# 04_MAIN_POWER.net
KiCad netlist of a schematic drawn in Altium Designer
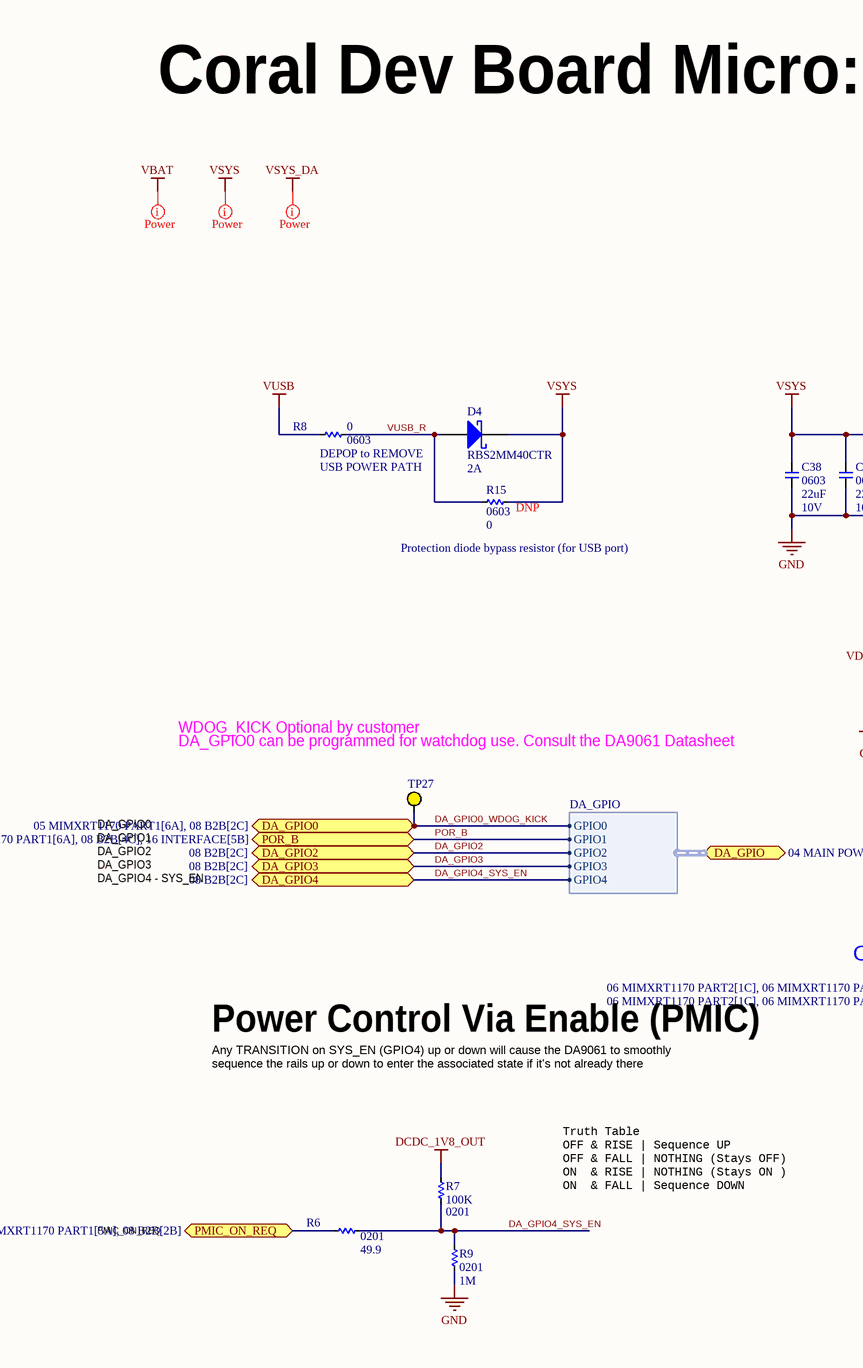
[diagram p0: 04 MAIN POWER.SchDoc, left]
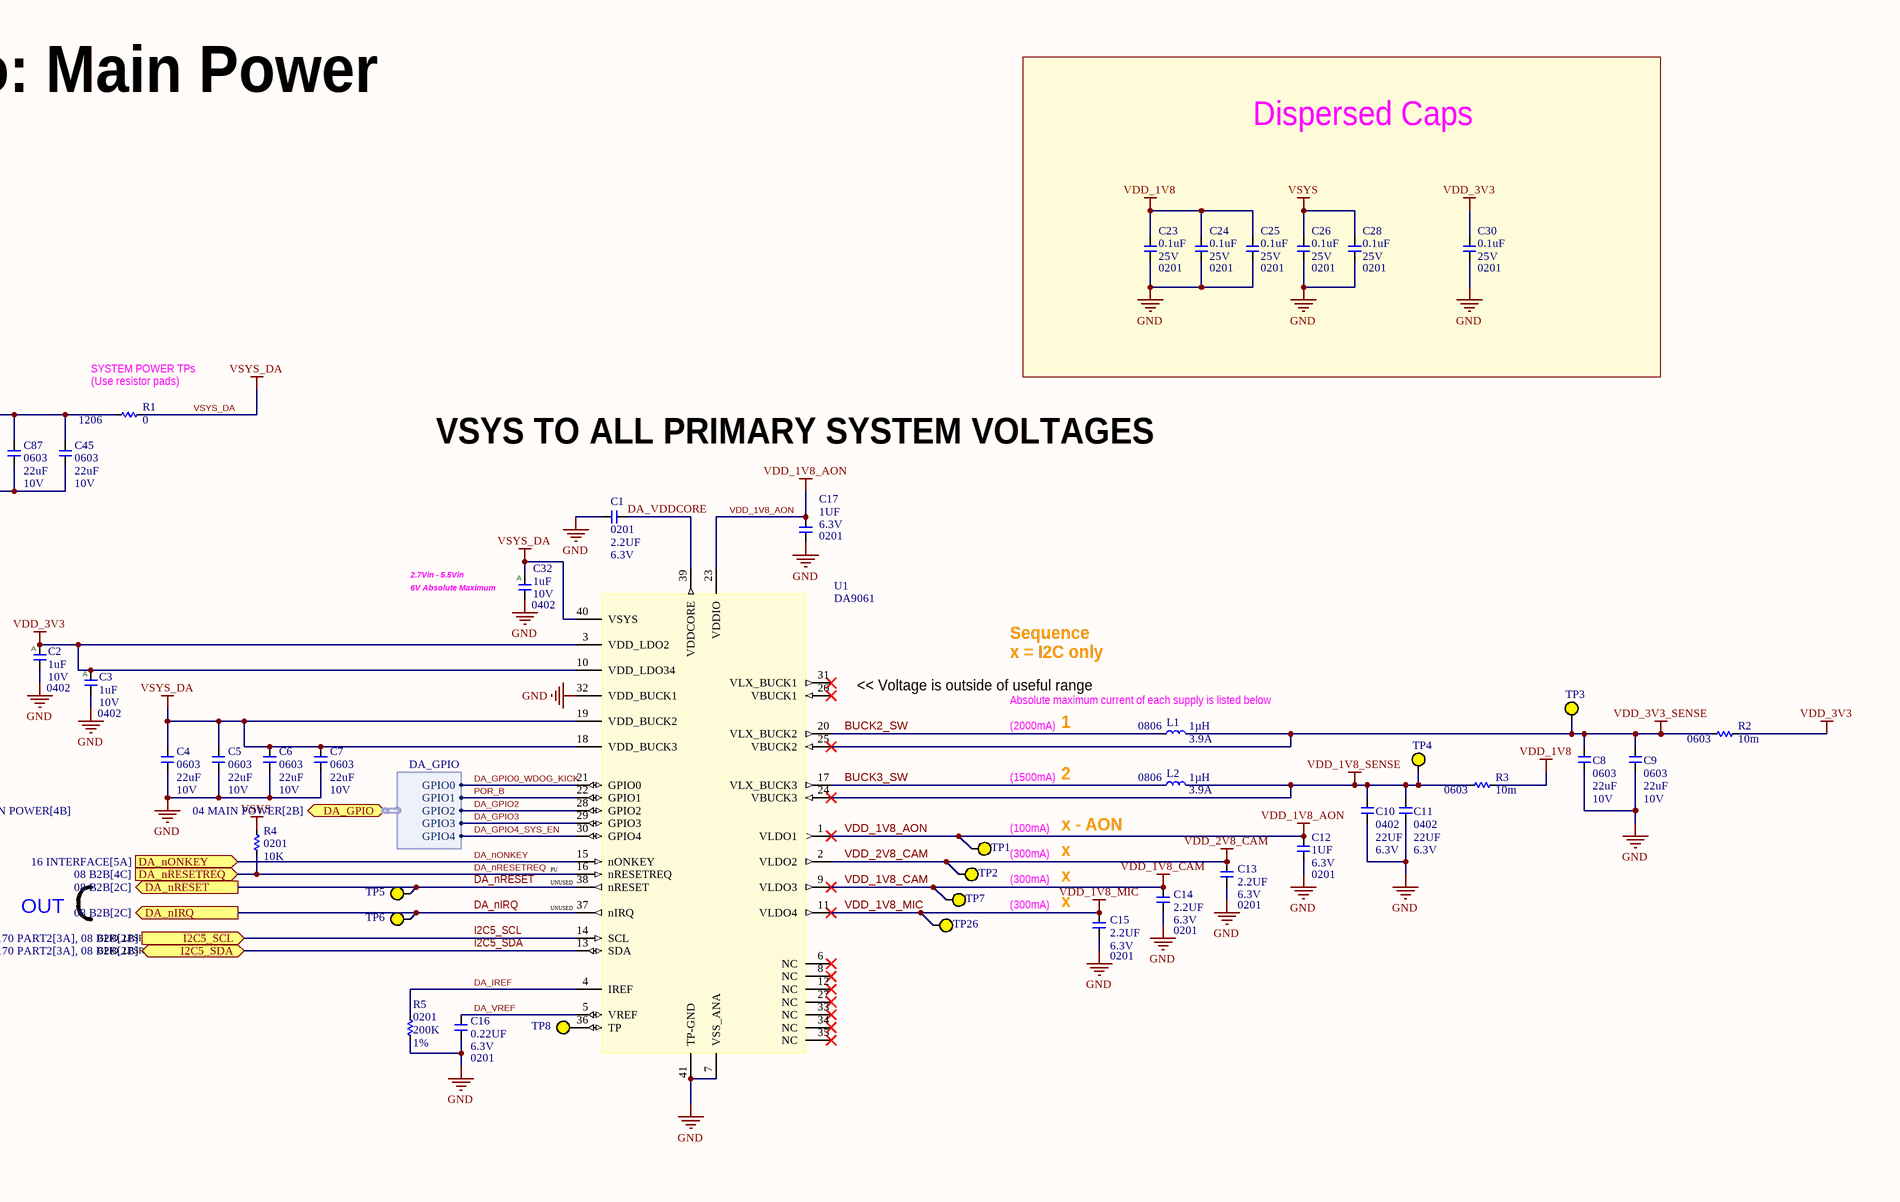
[diagram p1: 04 MAIN POWER.SchDoc, right]

(export (version "E")
  (design (tool "Eeschema 10.0.6"))
  (components
    (comp (ref "C1")
      (value "2.2UF")
      (footprint "C0201_H0.39MM")
      (description "CAP, CER, X5R, 2.2uF, 20%, 6.3V, 0201, 0.39mm")
      (fields
        (field (name "MFG") "YAGEO")
        (field (name "PACKAGE") "0201")
        (field (name "VOLTAGE") "6.3V")
        (field (name "TOLERANCE") "20%")
      )
      (libsource (lib "AltiumReleaseLibDB") (part "__Template_Cap"))
    )
    (comp (ref "C2")
      (value "1uF")
      (footprint "C0402")
      (description "CAP, CER, X5R, 1uF, 10V, 10%, 0402, AUTOGRADE")
      (fields
        (field (name "MFG") "Taiyo Yuden")
        (field (name "PACKAGE") "0402")
        (field (name "VOLTAGE") "10V")
        (field (name "TOLERANCE") "10%")
      )
      (libsource (lib "AltiumReleaseLibDB") (part "__Template_Cap_Auto"))
    )
    (comp (ref "C3")
      (value "1uF")
      (footprint "C0402")
      (description "CAP, CER, X5R, 1uF, 10V, 10%, 0402, AUTOGRADE")
      (fields
        (field (name "MFG") "Taiyo Yuden")
        (field (name "PACKAGE") "0402")
        (field (name "VOLTAGE") "10V")
        (field (name "TOLERANCE") "10%")
      )
      (libsource (lib "AltiumReleaseLibDB") (part "__Template_Cap_Auto"))
    )
    (comp (ref "C4")
      (value "22uF")
      (footprint "C0603")
      (description "CAP, CER, X5R, 22uF, 20%, 10V, 0603")
      (fields
        (field (name "MFG") "TDK")
        (field (name "PACKAGE") "0603")
        (field (name "VOLTAGE") "10V")
        (field (name "TOLERANCE") "20%")
      )
      (libsource (lib "AltiumReleaseLibDB") (part "__Template_Cap"))
    )
    (comp (ref "C5")
      (value "22uF")
      (footprint "C0603")
      (description "CAP, CER, X5R, 22uF, 20%, 10V, 0603")
      (fields
        (field (name "MFG") "TDK")
        (field (name "PACKAGE") "0603")
        (field (name "VOLTAGE") "10V")
        (field (name "TOLERANCE") "20%")
      )
      (libsource (lib "AltiumReleaseLibDB") (part "__Template_Cap"))
    )
    (comp (ref "C6")
      (value "22uF")
      (footprint "C0603")
      (description "CAP, CER, X5R, 22uF, 20%, 10V, 0603")
      (fields
        (field (name "MFG") "TDK")
        (field (name "PACKAGE") "0603")
        (field (name "VOLTAGE") "10V")
        (field (name "TOLERANCE") "20%")
      )
      (libsource (lib "AltiumReleaseLibDB") (part "__Template_Cap"))
    )
    (comp (ref "C7")
      (value "22uF")
      (footprint "C0603")
      (description "CAP, CER, X5R, 22uF, 20%, 10V, 0603")
      (fields
        (field (name "MFG") "TDK")
        (field (name "PACKAGE") "0603")
        (field (name "VOLTAGE") "10V")
        (field (name "TOLERANCE") "20%")
      )
      (libsource (lib "AltiumReleaseLibDB") (part "__Template_Cap"))
    )
    (comp (ref "C8")
      (value "22uF")
      (footprint "C0603")
      (description "CAP, CER, X5R, 22uF, 20%, 10V, 0603")
      (fields
        (field (name "MFG") "TDK")
        (field (name "PACKAGE") "0603")
        (field (name "VOLTAGE") "10V")
        (field (name "TOLERANCE") "20%")
      )
      (libsource (lib "AltiumReleaseLibDB") (part "__Template_Cap"))
    )
    (comp (ref "C9")
      (value "22uF")
      (footprint "C0603")
      (description "CAP, CER, X5R, 22uF, 20%, 10V, 0603")
      (fields
        (field (name "MFG") "TDK")
        (field (name "PACKAGE") "0603")
        (field (name "VOLTAGE") "10V")
        (field (name "TOLERANCE") "20%")
      )
      (libsource (lib "AltiumReleaseLibDB") (part "__Template_Cap"))
    )
    (comp (ref "C10")
      (value "22UF")
      (footprint "C0402")
      (description "CAP, CER, X5R, 22uF, 20%, 6.3V, 0402")
      (fields
        (field (name "MFG") "AVX")
        (field (name "PACKAGE") "0402")
        (field (name "VOLTAGE") "6.3V")
        (field (name "TOLERANCE") "20%")
      )
      (libsource (lib "AltiumReleaseLibDB") (part "__Template_Cap"))
    )
    (comp (ref "C11")
      (value "22UF")
      (footprint "C0402")
      (description "CAP, CER, X5R, 22uF, 20%, 6.3V, 0402")
      (fields
        (field (name "MFG") "AVX")
        (field (name "PACKAGE") "0402")
        (field (name "VOLTAGE") "6.3V")
        (field (name "TOLERANCE") "20%")
      )
      (libsource (lib "AltiumReleaseLibDB") (part "__Template_Cap"))
    )
    (comp (ref "C12")
      (value "1UF")
      (footprint "C0201_H0.39MM")
      (description "CAP, CER, X6S, 1uF, 20%, 6.3V, 0201, 0.39mm")
      (fields
        (field (name "MFG") "MURATA")
        (field (name "PACKAGE") "0201")
        (field (name "VOLTAGE") "6.3V")
        (field (name "TOLERANCE") "20%")
      )
      (libsource (lib "AltiumReleaseLibDB") (part "__Template_Cap"))
    )
    (comp (ref "C13")
      (value "2.2UF")
      (footprint "C0201_H0.39MM")
      (description "CAP, CER, X5R, 2.2uF, 20%, 6.3V, 0201, 0.39mm")
      (fields
        (field (name "MFG") "YAGEO")
        (field (name "PACKAGE") "0201")
        (field (name "VOLTAGE") "6.3V")
        (field (name "TOLERANCE") "20%")
      )
      (libsource (lib "AltiumReleaseLibDB") (part "__Template_Cap"))
    )
    (comp (ref "C14")
      (value "2.2UF")
      (footprint "C0201_H0.39MM")
      (description "CAP, CER, X5R, 2.2uF, 20%, 6.3V, 0201, 0.39mm")
      (fields
        (field (name "MFG") "YAGEO")
        (field (name "PACKAGE") "0201")
        (field (name "VOLTAGE") "6.3V")
        (field (name "TOLERANCE") "20%")
      )
      (libsource (lib "AltiumReleaseLibDB") (part "__Template_Cap"))
    )
    (comp (ref "C15")
      (value "2.2UF")
      (footprint "C0201_H0.39MM")
      (description "CAP, CER, X5R, 2.2uF, 20%, 6.3V, 0201, 0.39mm")
      (fields
        (field (name "MFG") "YAGEO")
        (field (name "PACKAGE") "0201")
        (field (name "VOLTAGE") "6.3V")
        (field (name "TOLERANCE") "20%")
      )
      (libsource (lib "AltiumReleaseLibDB") (part "__Template_Cap"))
    )
    (comp (ref "C16")
      (value "0.22UF")
      (footprint "C0201")
      (description "CAP, CER, X5R, 0.22uF, 6.3V, 10%, 0201, 0.33mm T")
      (fields
        (field (name "MFG") "TDK")
        (field (name "PACKAGE") "0201")
        (field (name "VOLTAGE") "6.3V")
        (field (name "TOLERANCE") "10%")
      )
      (libsource (lib "AltiumReleaseLibDB") (part "__Template_Cap"))
    )
    (comp (ref "C17")
      (value "1UF")
      (footprint "C0201_H0.39MM")
      (description "CAP, CER, X6S, 1uF, 20%, 6.3V, 0201, 0.39mm")
      (fields
        (field (name "MFG") "MURATA")
        (field (name "PACKAGE") "0201")
        (field (name "VOLTAGE") "6.3V")
        (field (name "TOLERANCE") "20%")
      )
      (libsource (lib "AltiumReleaseLibDB") (part "__Template_Cap"))
    )
    (comp (ref "C23")
      (value "0.1uF")
      (footprint "C0201Y")
      (description "CAP, CER, X5R, 0.1uF, 25V, 20%, 0201, 0.33mm T")
      (fields
        (field (name "MFG") "MURATA")
        (field (name "PACKAGE") "0201")
        (field (name "VOLTAGE") "25V")
        (field (name "TOLERANCE") "20%")
      )
      (libsource (lib "AltiumReleaseLibDB") (part "__Template_Cap"))
    )
    (comp (ref "C24")
      (value "0.1uF")
      (footprint "C0201Y")
      (description "CAP, CER, X5R, 0.1uF, 25V, 20%, 0201, 0.33mm T")
      (fields
        (field (name "MFG") "MURATA")
        (field (name "PACKAGE") "0201")
        (field (name "VOLTAGE") "25V")
        (field (name "TOLERANCE") "20%")
      )
      (libsource (lib "AltiumReleaseLibDB") (part "__Template_Cap"))
    )
    (comp (ref "C25")
      (value "0.1uF")
      (footprint "C0201Y")
      (description "CAP, CER, X5R, 0.1uF, 25V, 20%, 0201, 0.33mm T")
      (fields
        (field (name "MFG") "MURATA")
        (field (name "PACKAGE") "0201")
        (field (name "VOLTAGE") "25V")
        (field (name "TOLERANCE") "20%")
      )
      (libsource (lib "AltiumReleaseLibDB") (part "__Template_Cap"))
    )
    (comp (ref "C26")
      (value "0.1uF")
      (footprint "C0201Y")
      (description "CAP, CER, X5R, 0.1uF, 25V, 20%, 0201, 0.33mm T")
      (fields
        (field (name "MFG") "MURATA")
        (field (name "PACKAGE") "0201")
        (field (name "VOLTAGE") "25V")
        (field (name "TOLERANCE") "20%")
      )
      (libsource (lib "AltiumReleaseLibDB") (part "__Template_Cap"))
    )
    (comp (ref "C28")
      (value "0.1uF")
      (footprint "C0201Y")
      (description "CAP, CER, X5R, 0.1uF, 25V, 20%, 0201, 0.33mm T")
      (fields
        (field (name "MFG") "MURATA")
        (field (name "PACKAGE") "0201")
        (field (name "VOLTAGE") "25V")
        (field (name "TOLERANCE") "20%")
      )
      (libsource (lib "AltiumReleaseLibDB") (part "__Template_Cap"))
    )
    (comp (ref "C30")
      (value "0.1uF")
      (footprint "C0201Y")
      (description "CAP, CER, X5R, 0.1uF, 25V, 20%, 0201, 0.33mm T")
      (fields
        (field (name "MFG") "MURATA")
        (field (name "PACKAGE") "0201")
        (field (name "VOLTAGE") "25V")
        (field (name "TOLERANCE") "20%")
      )
      (libsource (lib "AltiumReleaseLibDB") (part "__Template_Cap"))
    )
    (comp (ref "C32")
      (value "1uF")
      (footprint "C0402")
      (description "CAP, CER, X5R, 1uF, 10V, 10%, 0402, AUTOGRADE")
      (fields
        (field (name "MFG") "Taiyo Yuden")
        (field (name "PACKAGE") "0402")
        (field (name "VOLTAGE") "10V")
        (field (name "TOLERANCE") "10%")
      )
      (libsource (lib "AltiumReleaseLibDB") (part "__Template_Cap_Auto"))
    )
    (comp (ref "C38")
      (value "22uF")
      (footprint "C0603")
      (description "CAP, CER, X5R, 22uF, 20%, 10V, 0603")
      (fields
        (field (name "MFG") "TDK")
        (field (name "PACKAGE") "0603")
        (field (name "VOLTAGE") "10V")
        (field (name "TOLERANCE") "20%")
      )
      (libsource (lib "AltiumReleaseLibDB") (part "__Template_Cap"))
    )
    (comp (ref "C45")
      (value "22uF")
      (footprint "C0603")
      (description "CAP, CER, X5R, 22uF, 20%, 10V, 0603")
      (fields
        (field (name "MFG") "TDK")
        (field (name "PACKAGE") "0603")
        (field (name "VOLTAGE") "10V")
        (field (name "TOLERANCE") "20%")
      )
      (libsource (lib "AltiumReleaseLibDB") (part "__Template_Cap"))
    )
    (comp (ref "C87")
      (value "22uF")
      (footprint "C0603")
      (description "CAP, CER, X5R, 22uF, 20%, 10V, 0603")
      (fields
        (field (name "MFG") "TDK")
        (field (name "PACKAGE") "0603")
        (field (name "VOLTAGE") "10V")
        (field (name "TOLERANCE") "20%")
      )
      (libsource (lib "AltiumReleaseLibDB") (part "__Template_Cap"))
    )
    (comp (ref "D4")
      (value "RBS2MM40CTR")
      (footprint "SOD123_AK")
      (description "DIODE, SCHOTTKY, 20V VRRM, 2A IO, 45A SURGE, SOD-123F")
      (fields
        (field (name "MFG") "Rohm Semiconductor")
        (field (name "CURRENT - AVERAGE RECTIFIED (IO)") "2A")
        (field (name "Comment") "__Template_DIODE_SCHOTTKY")
      )
      (libsource (lib "AltiumReleaseLibDB") (part "__Template_DIODE_SCHOTTKY"))
    )
    (comp (ref "L1")
      (value "1µH")
      (footprint "L2016_H1.0MM")
      (description "IND, PWR, FILM, 1uH, 20%, 3.9A Isat, 3.1A Idc, 0.056 DCR, 2016m, 1.00mm")
      (fields
        (field (name "MFG") "TDK")
        (field (name "PACKAGE") "0806")
        (field (name "TOLERANCE") "20")
        (field (name "ISAT") "3.9A")
      )
      (libsource (lib "AltiumReleaseLibDB") (part "__Template_Inductor"))
    )
    (comp (ref "L2")
      (value "1µH")
      (footprint "L2016_H1.0MM")
      (description "IND, PWR, FILM, 1uH, 20%, 3.9A Isat, 3.1A Idc, 0.056 DCR, 2016m, 1.00mm")
      (fields
        (field (name "MFG") "TDK")
        (field (name "PACKAGE") "0806")
        (field (name "TOLERANCE") "20")
        (field (name "ISAT") "3.9A")
      )
      (libsource (lib "AltiumReleaseLibDB") (part "__Template_Inductor"))
    )
    (comp (ref "R1")
      (value "0")
      (footprint "R1206")
      (description "RES, 0, 5%, 1/4W, 1206")
      (fields (field (name "MFG") "ROHM") (field (name "PACKAGE") "1206") (field (name "POWER") "1/4W"))
      (libsource (lib "AltiumReleaseLibDB") (part "__Template_Resistor"))
    )
    (comp (ref "R2")
      (value "10m")
      (footprint "R0603")
      (description "Resistor, 10.0m Ohms, 0603, 0.1W, ±1%")
      (fields (field (name "MFG") "VISHAY") (field (name "PACKAGE") "0603") (field (name "POWER") "1/10W"))
      (libsource (lib "AltiumReleaseLibDB") (part "__Template_Resistor"))
    )
    (comp (ref "R3")
      (value "10m")
      (footprint "R0603")
      (description "Resistor, 10.0m Ohms, 0603, 0.1W, ±1%")
      (fields (field (name "MFG") "VISHAY") (field (name "PACKAGE") "0603") (field (name "POWER") "1/10W"))
      (libsource (lib "AltiumReleaseLibDB") (part "__Template_Resistor"))
    )
    (comp (ref "R4")
      (value "10K")
      (footprint "R0201")
      (description "RES, 10K, 1%, 1/20W, 0201")
      (fields (field (name "MFG") "YAGEO") (field (name "PACKAGE") "0201") (field (name "POWER") "1/20W"))
      (libsource (lib "AltiumReleaseLibDB") (part "__Template_Resistor"))
    )
    (comp (ref "R5")
      (value "200K")
      (footprint "R0201")
      (description "Resistor, 200K Ohms, 0201, 0.05W, ±1%")
      (fields
        (field (name "MFG") "VISHAY")
        (field (name "PACKAGE") "0201")
        (field (name "POWER") "1/20W")
        (field (name "TOLERANCE") "1%")
      )
      (libsource (lib "AltiumReleaseLibDB") (part "__Template_Resistor"))
    )
    (comp (ref "R6")
      (value "49.9")
      (footprint "R0201")
      (description "RES, 49.9, 1%, 1/20W, 0201")
      (fields (field (name "MFG") "PANASONIC") (field (name "PACKAGE") "0201") (field (name "POWER") "1/20W"))
      (libsource (lib "AltiumReleaseLibDB") (part "__Template_Resistor"))
    )
    (comp (ref "R7")
      (value "100K")
      (footprint "R0201")
      (description "RES, 100K, 1%, 1/20W, 0201")
      (fields (field (name "MFG") "PANASONIC") (field (name "PACKAGE") "0201") (field (name "POWER") "1/20W"))
      (libsource (lib "AltiumReleaseLibDB") (part "__Template_Resistor"))
    )
    (comp (ref "R8")
      (value "0")
      (footprint "R0603")
      (description "RES, 0, JUMPER, 1/8W, 0603")
      (fields (field (name "MFG") "VISHAY") (field (name "PACKAGE") "0603") (field (name "POWER") "1/8W"))
      (libsource (lib "AltiumReleaseLibDB") (part "__Template_Resistor"))
    )
    (comp (ref "R9")
      (value "1M")
      (footprint "R0201")
      (description "RES, 1M, 1%, 1/20W, 0201")
      (fields (field (name "MFG") "PANASONIC") (field (name "PACKAGE") "0201") (field (name "POWER") "1/20W"))
      (libsource (lib "AltiumReleaseLibDB") (part "__Template_Resistor"))
    )
    (comp (ref "R15")
      (value "0")
      (footprint "R0603")
      (description "RES, 0, JUMPER, 1/8W, 0603")
      (fields
        (field (name "MFG") "VISHAY")
        (field (name "PACKAGE") "0603")
        (field (name "POWER") "1/8W")
        (field (name "DNP") "DNP")
      )
      (libsource (lib "AltiumReleaseLibDB") (part "__Template_Resistor"))
    )
    (comp (ref "TP1")
      (value "TESTPAD_30MIL")
      (footprint "TESTPAD_SMT_30MIL")
      (description "TESTPAD_SMT_30MIL")
      (fields (field (name "MFG") "_PCB Feature"))
      (libsource (lib "AltiumReleaseLibDB") (part "TESTPAD_30MIL"))
    )
    (comp (ref "TP2")
      (value "TESTPAD_30MIL")
      (footprint "TESTPAD_SMT_30MIL")
      (description "TESTPAD_SMT_30MIL")
      (fields (field (name "MFG") "_PCB Feature"))
      (libsource (lib "AltiumReleaseLibDB") (part "TESTPAD_30MIL"))
    )
    (comp (ref "TP3")
      (value "TESTPAD_30MIL")
      (footprint "TESTPAD_SMT_30MIL")
      (description "TESTPAD_SMT_30MIL")
      (fields (field (name "MFG") "_PCB Feature"))
      (libsource (lib "AltiumReleaseLibDB") (part "TESTPAD_30MIL"))
    )
    (comp (ref "TP4")
      (value "TESTPAD_30MIL")
      (footprint "TESTPAD_SMT_30MIL")
      (description "TESTPAD_SMT_30MIL")
      (fields (field (name "MFG") "_PCB Feature"))
      (libsource (lib "AltiumReleaseLibDB") (part "TESTPAD_30MIL"))
    )
    (comp (ref "TP5")
      (value "TESTPAD_30MIL")
      (footprint "TESTPAD_SMT_30MIL")
      (description "TESTPAD_SMT_30MIL")
      (fields (field (name "MFG") "_PCB Feature"))
      (libsource (lib "AltiumReleaseLibDB") (part "TESTPAD_30MIL"))
    )
    (comp (ref "TP6")
      (value "TESTPAD_30MIL")
      (footprint "TESTPAD_SMT_30MIL")
      (description "TESTPAD_SMT_30MIL")
      (fields (field (name "MFG") "_PCB Feature"))
      (libsource (lib "AltiumReleaseLibDB") (part "TESTPAD_30MIL"))
    )
    (comp (ref "TP7")
      (value "TESTPAD_30MIL")
      (footprint "TESTPAD_SMT_30MIL")
      (description "TESTPAD_SMT_30MIL")
      (fields (field (name "MFG") "_PCB Feature"))
      (libsource (lib "AltiumReleaseLibDB") (part "TESTPAD_30MIL"))
    )
    (comp (ref "TP8")
      (value "TESTPAD_30MIL")
      (footprint "TESTPAD_SMT_30MIL")
      (description "TESTPAD_SMT_30MIL")
      (fields (field (name "MFG") "_PCB Feature"))
      (libsource (lib "AltiumReleaseLibDB") (part "TESTPAD_30MIL"))
    )
    (comp (ref "TP26")
      (value "TESTPAD_30MIL")
      (footprint "TESTPAD_SMT_30MIL")
      (description "TESTPAD_SMT_30MIL")
      (fields (field (name "MFG") "_PCB Feature"))
      (libsource (lib "AltiumReleaseLibDB") (part "TESTPAD_30MIL"))
    )
    (comp (ref "TP27")
      (value "TESTPAD_30MIL")
      (footprint "TESTPAD_SMT_30MIL")
      (description "TESTPAD_SMT_30MIL")
      (fields (field (name "MFG") "_PCB Feature"))
      (libsource (lib "AltiumReleaseLibDB") (part "TESTPAD_30MIL"))
    )
    (comp (ref "U1")
      (value "PMIC_DIALOG_SEMI_DA9061")
      (footprint "QFN50P600X600X90-40-TP")
      (description "IC, PWR MANAGEMENT, DA9061, DDR, BUCK, LDO, 2.7 TO 5.5 VIN, SMD")
      (fields (field (name "MFG") "Dialog Semiconductor") (field (name "MFG P/N") "DA9061"))
      (libsource (lib "AltiumReleaseLibDB") (part "PMIC_DIALOG_SEMI_DA9061"))
    )
  )
  (nets
    (net (code "2") (name "/BUCK2_SW") (class "Default")
      (node (ref "L1") (pin "1") (pintype "passive"))
      (node (ref "U1") (pin "20") (pinfunction "VLX_BUCK2_20") (pintype "output"))
    )
    (net (code "3") (name "/BUCK3_SW") (class "Default")
      (node (ref "L2") (pin "1") (pintype "passive"))
      (node (ref "U1") (pin "17") (pinfunction "VLX_BUCK3_17") (pintype "output"))
    )
    (net (code "4") (name "/DA_GPIO0_WDOG_KICK") (class "Default")
      (node (ref "TP27") (pin "1") (pintype "passive"))
      (node (ref "U1") (pin "21") (pinfunction "GPIO0_21") (pintype "bidirectional"))
    )
    (net (code "5") (name "/DA_GPIO2") (class "Default")
      (node (ref "U1") (pin "28") (pinfunction "GPIO2_28") (pintype "bidirectional"))
    )
    (net (code "6") (name "/DA_GPIO3") (class "Default")
      (node (ref "U1") (pin "29") (pinfunction "GPIO3_29") (pintype "bidirectional"))
    )
    (net (code "7") (name "/DA_GPIO4_SYS_EN") (class "Default")
      (node (ref "R6") (pin "2") (pintype "passive"))
      (node (ref "R7") (pin "1") (pintype "passive"))
      (node (ref "R9") (pin "2") (pintype "passive"))
      (node (ref "U1") (pin "30") (pinfunction "GPIO4_30") (pintype "bidirectional"))
    )
    (net (code "8") (name "/DA_IREF") (class "Default")
      (node (ref "R5") (pin "2") (pintype "passive"))
      (node (ref "U1") (pin "4") (pinfunction "IREF_4") (pintype "power_in"))
    )
    (net (code "9") (name "/DA_VDDCORE") (class "Default")
      (node (ref "C1") (pin "2") (pintype "passive"))
      (node (ref "U1") (pin "39") (pinfunction "VDDCORE_39") (pintype "output"))
    )
    (net (code "10") (name "/DA_VREF") (class "Default")
      (node (ref "C16") (pin "1") (pintype "passive"))
      (node (ref "U1") (pin "5") (pinfunction "VREF_5") (pintype "bidirectional"))
    )
    (net (code "11") (name "/DA_nIRQ") (class "Default")
      (node (ref "TP6") (pin "1") (pintype "passive"))
      (node (ref "U1") (pin "37") (pinfunction "nIRQ_37") (pintype "output"))
    )
    (net (code "12") (name "/DA_nONKEY") (class "Default")
      (node (ref "U1") (pin "15") (pinfunction "nONKEY_15") (pintype "input"))
    )
    (net (code "13") (name "/DA_nRESET") (class "Default")
      (node (ref "TP5") (pin "1") (pintype "passive"))
      (node (ref "U1") (pin "38") (pinfunction "nRESET_38") (pintype "output"))
    )
    (net (code "14") (name "/DA_nRESETREQ") (class "Default")
      (node (ref "R4") (pin "1") (pintype "passive"))
      (node (ref "U1") (pin "16") (pinfunction "nRESETREQ_16") (pintype "input"))
    )
    (net (code "15") (name "/I2C5_SCL") (class "Default")
      (node (ref "U1") (pin "14") (pinfunction "SCL_14") (pintype "input"))
    )
    (net (code "16") (name "/I2C5_SDA") (class "Default")
      (node (ref "U1") (pin "13") (pinfunction "SDA_13") (pintype "bidirectional"))
    )
    (net (code "17") (name "/PMIC_ON_REQ") (class "Default") (node (ref "R6") (pin "1") (pintype "passive")))
    (net (code "18") (name "/POR_B") (class "Default")
      (node (ref "U1") (pin "22") (pinfunction "GPIO1_22") (pintype "bidirectional"))
    )
    (net (code "19") (name "/VUSB_R") (class "Default")
      (node (ref "D4") (pin "A") (pinfunction "A_A") (pintype "passive"))
      (node (ref "R15") (pin "2") (pintype "passive"))
      (node (ref "R8") (pin "1") (pintype "passive"))
    )
    (net (code "21") (name "DCDC_1V8_OUT") (class "Default") (node (ref "R7") (pin "2") (pintype "passive")))
    (net (code "22") (name "GND") (class "Default")
      (node (ref "C1") (pin "1") (pintype "passive"))
      (node (ref "C10") (pin "2") (pintype "passive"))
      (node (ref "C11") (pin "2") (pintype "passive"))
      (node (ref "C12") (pin "2") (pintype "passive"))
      (node (ref "C13") (pin "2") (pintype "passive"))
      (node (ref "C14") (pin "2") (pintype "passive"))
      (node (ref "C15") (pin "2") (pintype "passive"))
      (node (ref "C16") (pin "2") (pintype "passive"))
      (node (ref "C17") (pin "2") (pintype "passive"))
      (node (ref "C2") (pin "2") (pintype "passive"))
      (node (ref "C23") (pin "2") (pintype "passive"))
      (node (ref "C24") (pin "2") (pintype "passive"))
      (node (ref "C25") (pin "2") (pintype "passive"))
      (node (ref "C26") (pin "2") (pintype "passive"))
      (node (ref "C28") (pin "2") (pintype "passive"))
      (node (ref "C3") (pin "2") (pintype "passive"))
      (node (ref "C30") (pin "2") (pintype "passive"))
      (node (ref "C32") (pin "2") (pintype "passive"))
      (node (ref "C38") (pin "2") (pintype "passive"))
      (node (ref "C4") (pin "2") (pintype "passive"))
      (node (ref "C45") (pin "2") (pintype "passive"))
      (node (ref "C5") (pin "2") (pintype "passive"))
      (node (ref "C6") (pin "2") (pintype "passive"))
      (node (ref "C7") (pin "2") (pintype "passive"))
      (node (ref "C8") (pin "2") (pintype "passive"))
      (node (ref "C87") (pin "2") (pintype "passive"))
      (node (ref "C9") (pin "2") (pintype "passive"))
      (node (ref "R5") (pin "1") (pintype "passive"))
      (node (ref "R9") (pin "1") (pintype "passive"))
      (node (ref "U1") (pin "32") (pinfunction "VDD_BUCK1_32") (pintype "power_in"))
      (node (ref "U1") (pin "41") (pinfunction "TP-GND_41") (pintype "power_in"))
      (node (ref "U1") (pin "7") (pinfunction "VSS_ANA_7") (pintype "power_in"))
    )
    (net (code "23") (name "Net-(U1-TP)") (class "Default")
      (node (ref "TP8") (pin "1") (pintype "passive"))
      (node (ref "U1") (pin "36") (pinfunction "TP_36") (pintype "bidirectional"))
    )
    (net (code "25") (name "VDD_1V8") (class "Default")
      (node (ref "C23") (pin "1") (pintype "passive"))
      (node (ref "C24") (pin "1") (pintype "passive"))
      (node (ref "C25") (pin "1") (pintype "passive"))
      (node (ref "R3") (pin "2") (pintype "passive"))
    )
    (net (code "26") (name "VDD_1V8_AON") (class "Default")
      (node (ref "C12") (pin "1") (pintype "passive"))
      (node (ref "C17") (pin "1") (pintype "passive"))
      (node (ref "TP1") (pin "1") (pintype "passive"))
      (node (ref "U1") (pin "1") (pinfunction "VLDO1_1") (pintype "output"))
      (node (ref "U1") (pin "23") (pinfunction "VDDIO_23") (pintype "power_in"))
    )
    (net (code "27") (name "VDD_1V8_CAM") (class "Default")
      (node (ref "C14") (pin "1") (pintype "passive"))
      (node (ref "TP7") (pin "1") (pintype "passive"))
      (node (ref "U1") (pin "9") (pinfunction "VLDO3_9") (pintype "output"))
    )
    (net (code "28") (name "VDD_1V8_MIC") (class "Default")
      (node (ref "C15") (pin "1") (pintype "passive"))
      (node (ref "TP26") (pin "1") (pintype "passive"))
      (node (ref "U1") (pin "11") (pinfunction "VLDO4_11") (pintype "output"))
    )
    (net (code "29") (name "VDD_1V8_SENSE") (class "Default")
      (node (ref "C10") (pin "1") (pintype "passive"))
      (node (ref "C11") (pin "1") (pintype "passive"))
      (node (ref "L2") (pin "2") (pintype "passive"))
      (node (ref "R3") (pin "1") (pintype "passive"))
      (node (ref "TP4") (pin "1") (pintype "passive"))
      (node (ref "U1") (pin "24") (pinfunction "VBUCK3_24") (pintype "input"))
    )
    (net (code "30") (name "VDD_2V8_CAM") (class "Default")
      (node (ref "C13") (pin "1") (pintype "passive"))
      (node (ref "TP2") (pin "1") (pintype "passive"))
      (node (ref "U1") (pin "2") (pinfunction "VLDO2_2") (pintype "output"))
    )
    (net (code "31") (name "VDD_3V3") (class "Default")
      (node (ref "C2") (pin "1") (pintype "passive"))
      (node (ref "C3") (pin "1") (pintype "passive"))
      (node (ref "C30") (pin "1") (pintype "passive"))
      (node (ref "R2") (pin "2") (pintype "passive"))
      (node (ref "U1") (pin "10") (pinfunction "VDD_LDO34_10") (pintype "power_in"))
      (node (ref "U1") (pin "3") (pinfunction "VDD_LDO2_3") (pintype "power_in"))
    )
    (net (code "32") (name "VDD_3V3_SENSE") (class "Default")
      (node (ref "C8") (pin "1") (pintype "passive"))
      (node (ref "C9") (pin "1") (pintype "passive"))
      (node (ref "L1") (pin "2") (pintype "passive"))
      (node (ref "R2") (pin "1") (pintype "passive"))
      (node (ref "TP3") (pin "1") (pintype "passive"))
      (node (ref "U1") (pin "25") (pinfunction "VBUCK2_25") (pintype "input"))
    )
    (net (code "33") (name "VSYS") (class "Default")
      (node (ref "C26") (pin "1") (pintype "passive"))
      (node (ref "C28") (pin "1") (pintype "passive"))
      (node (ref "C38") (pin "1") (pintype "passive"))
      (node (ref "C45") (pin "1") (pintype "passive"))
      (node (ref "C87") (pin "1") (pintype "passive"))
      (node (ref "D4") (pin "K") (pinfunction "K_K") (pintype "passive"))
      (node (ref "R1") (pin "1") (pintype "passive"))
      (node (ref "R15") (pin "1") (pintype "passive"))
      (node (ref "R4") (pin "2") (pintype "passive"))
    )
    (net (code "34") (name "VSYS_DA") (class "Default")
      (node (ref "C32") (pin "1") (pintype "passive"))
      (node (ref "C4") (pin "1") (pintype "passive"))
      (node (ref "C5") (pin "1") (pintype "passive"))
      (node (ref "C6") (pin "1") (pintype "passive"))
      (node (ref "C7") (pin "1") (pintype "passive"))
      (node (ref "R1") (pin "2") (pintype "passive"))
      (node (ref "U1") (pin "18") (pinfunction "VDD_BUCK3_18") (pintype "power_in"))
      (node (ref "U1") (pin "19") (pinfunction "VDD_BUCK2_19") (pintype "power_in"))
      (node (ref "U1") (pin "40") (pinfunction "VSYS_40") (pintype "power_in"))
    )
    (net (code "35") (name "VUSB") (class "Default") (node (ref "R8") (pin "2") (pintype "passive")))
    (net (code "36") (name "unconnected-(U1-NC-Pad6)") (class "Default")
      (node (ref "U1") (pin "6") (pinfunction "NC_6") (pintype "passive+no_connect"))
    )
    (net (code "37") (name "unconnected-(U1-NC-Pad8)") (class "Default")
      (node (ref "U1") (pin "8") (pinfunction "NC_8") (pintype "passive+no_connect"))
    )
    (net (code "38") (name "unconnected-(U1-NC-Pad12)") (class "Default")
      (node (ref "U1") (pin "12") (pinfunction "NC_12") (pintype "passive+no_connect"))
    )
    (net (code "39") (name "unconnected-(U1-NC-Pad27)") (class "Default")
      (node (ref "U1") (pin "27") (pinfunction "NC_27") (pintype "passive+no_connect"))
    )
    (net (code "40") (name "unconnected-(U1-NC-Pad33)") (class "Default")
      (node (ref "U1") (pin "33") (pinfunction "NC_33") (pintype "passive+no_connect"))
    )
    (net (code "41") (name "unconnected-(U1-NC-Pad34)") (class "Default")
      (node (ref "U1") (pin "34") (pinfunction "NC_34") (pintype "passive+no_connect"))
    )
    (net (code "42") (name "unconnected-(U1-NC-Pad35)") (class "Default")
      (node (ref "U1") (pin "35") (pinfunction "NC_35") (pintype "passive+no_connect"))
    )
    (net (code "43") (name "unconnected-(U1-VBUCK1-Pad26)") (class "Default")
      (node (ref "U1") (pin "26") (pinfunction "VBUCK1_26") (pintype "input+no_connect"))
    )
    (net (code "44") (name "unconnected-(U1-VLX_BUCK1-Pad31)") (class "Default")
      (node (ref "U1") (pin "31") (pinfunction "VLX_BUCK1_31") (pintype "output+no_connect"))
    )
  )
)
